# Led_Strip_5630.net
KiCad netlist of a schematic drawn in Altium Designer
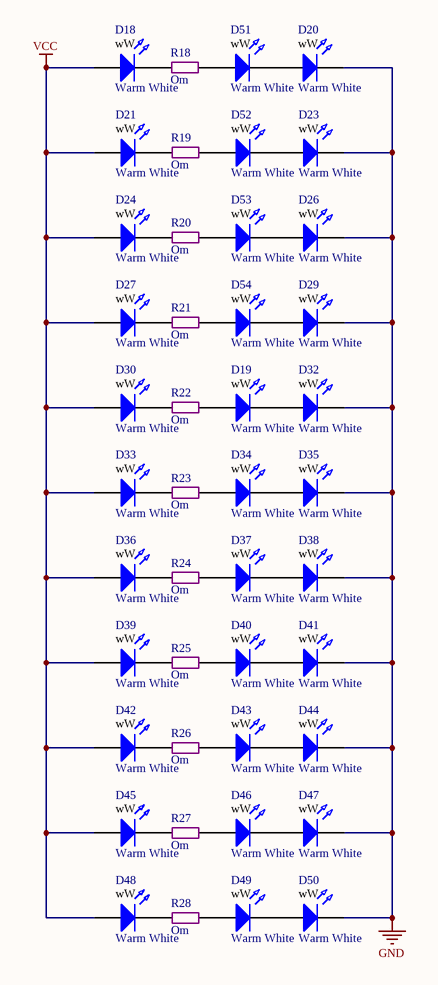
[diagram p0: Led Strip 5630.SchDoc]

(export (version "E")
  (design (tool "Eeschema 10.0.6"))
  (components
    (comp (ref "D18")
      (value "Warm White")
      (footprint "LED:LED SMD 5730 White")
      (description "?3v ?20mA")
      (libsource (lib "LED") (part "Led SMD White Warm"))
    )
    (comp (ref "D19")
      (value "Warm White")
      (footprint "LED:LED SMD 5730 White")
      (description "?3v ?20mA")
      (libsource (lib "LED") (part "Led SMD White Warm"))
    )
    (comp (ref "D20")
      (value "Warm White")
      (footprint "LED:LED SMD 5730 White")
      (description "?3v ?20mA")
      (libsource (lib "LED") (part "Led SMD White Warm"))
    )
    (comp (ref "D21")
      (value "Warm White")
      (footprint "LED:LED SMD 5730 White")
      (description "?3v ?20mA")
      (libsource (lib "LED") (part "Led SMD White Warm"))
    )
    (comp (ref "D23")
      (value "Warm White")
      (footprint "LED:LED SMD 5730 White")
      (description "?3v ?20mA")
      (libsource (lib "LED") (part "Led SMD White Warm"))
    )
    (comp (ref "D24")
      (value "Warm White")
      (footprint "LED:LED SMD 5730 White")
      (description "?3v ?20mA")
      (libsource (lib "LED") (part "Led SMD White Warm"))
    )
    (comp (ref "D26")
      (value "Warm White")
      (footprint "LED:LED SMD 5730 White")
      (description "?3v ?20mA")
      (libsource (lib "LED") (part "Led SMD White Warm"))
    )
    (comp (ref "D27")
      (value "Warm White")
      (footprint "LED:LED SMD 5730 White")
      (description "?3v ?20mA")
      (libsource (lib "LED") (part "Led SMD White Warm"))
    )
    (comp (ref "D29")
      (value "Warm White")
      (footprint "LED:LED SMD 5730 White")
      (description "?3v ?20mA")
      (libsource (lib "LED") (part "Led SMD White Warm"))
    )
    (comp (ref "D30")
      (value "Warm White")
      (footprint "LED:LED SMD 5730 White")
      (description "?3v ?20mA")
      (libsource (lib "LED") (part "Led SMD White Warm"))
    )
    (comp (ref "D32")
      (value "Warm White")
      (footprint "LED:LED SMD 5730 White")
      (description "?3v ?20mA")
      (libsource (lib "LED") (part "Led SMD White Warm"))
    )
    (comp (ref "D33")
      (value "Warm White")
      (footprint "LED:LED SMD 5730 White")
      (description "?3v ?20mA")
      (libsource (lib "LED") (part "Led SMD White Warm"))
    )
    (comp (ref "D34")
      (value "Warm White")
      (footprint "LED:LED SMD 5730 White")
      (description "?3v ?20mA")
      (libsource (lib "LED") (part "Led SMD White Warm"))
    )
    (comp (ref "D35")
      (value "Warm White")
      (footprint "LED:LED SMD 5730 White")
      (description "?3v ?20mA")
      (libsource (lib "LED") (part "Led SMD White Warm"))
    )
    (comp (ref "D36")
      (value "Warm White")
      (footprint "LED:LED SMD 5730 White")
      (description "?3v ?20mA")
      (libsource (lib "LED") (part "Led SMD White Warm"))
    )
    (comp (ref "D37")
      (value "Warm White")
      (footprint "LED:LED SMD 5730 White")
      (description "?3v ?20mA")
      (libsource (lib "LED") (part "Led SMD White Warm"))
    )
    (comp (ref "D38")
      (value "Warm White")
      (footprint "LED:LED SMD 5730 White")
      (description "?3v ?20mA")
      (libsource (lib "LED") (part "Led SMD White Warm"))
    )
    (comp (ref "D39")
      (value "Warm White")
      (footprint "LED:LED SMD 5730 White")
      (description "?3v ?20mA")
      (libsource (lib "LED") (part "Led SMD White Warm"))
    )
    (comp (ref "D40")
      (value "Warm White")
      (footprint "LED:LED SMD 5730 White")
      (description "?3v ?20mA")
      (libsource (lib "LED") (part "Led SMD White Warm"))
    )
    (comp (ref "D41")
      (value "Warm White")
      (footprint "LED:LED SMD 5730 White")
      (description "?3v ?20mA")
      (libsource (lib "LED") (part "Led SMD White Warm"))
    )
    (comp (ref "D42")
      (value "Warm White")
      (footprint "LED:LED SMD 5730 White")
      (description "?3v ?20mA")
      (libsource (lib "LED") (part "Led SMD White Warm"))
    )
    (comp (ref "D43")
      (value "Warm White")
      (footprint "LED:LED SMD 5730 White")
      (description "?3v ?20mA")
      (libsource (lib "LED") (part "Led SMD White Warm"))
    )
    (comp (ref "D44")
      (value "Warm White")
      (footprint "LED:LED SMD 5730 White")
      (description "?3v ?20mA")
      (libsource (lib "LED") (part "Led SMD White Warm"))
    )
    (comp (ref "D45")
      (value "Warm White")
      (footprint "LED:LED SMD 5730 White")
      (description "?3v ?20mA")
      (libsource (lib "LED") (part "Led SMD White Warm"))
    )
    (comp (ref "D46")
      (value "Warm White")
      (footprint "LED:LED SMD 5730 White")
      (description "?3v ?20mA")
      (libsource (lib "LED") (part "Led SMD White Warm"))
    )
    (comp (ref "D47")
      (value "Warm White")
      (footprint "LED:LED SMD 5730 White")
      (description "?3v ?20mA")
      (libsource (lib "LED") (part "Led SMD White Warm"))
    )
    (comp (ref "D48")
      (value "Warm White")
      (footprint "LED:LED SMD 5730 White")
      (description "?3v ?20mA")
      (libsource (lib "LED") (part "Led SMD White Warm"))
    )
    (comp (ref "D49")
      (value "Warm White")
      (footprint "LED:LED SMD 5730 White")
      (description "?3v ?20mA")
      (libsource (lib "LED") (part "Led SMD White Warm"))
    )
    (comp (ref "D50")
      (value "Warm White")
      (footprint "LED:LED SMD 5730 White")
      (description "?3v ?20mA")
      (libsource (lib "LED") (part "Led SMD White Warm"))
    )
    (comp (ref "D51")
      (value "Warm White")
      (footprint "LED:LED SMD 5730 White")
      (description "?3v ?20mA")
      (libsource (lib "LED") (part "Led SMD White Warm"))
    )
    (comp (ref "D52")
      (value "Warm White")
      (footprint "LED:LED SMD 5730 White")
      (description "?3v ?20mA")
      (libsource (lib "LED") (part "Led SMD White Warm"))
    )
    (comp (ref "D53")
      (value "Warm White")
      (footprint "LED:LED SMD 5730 White")
      (description "?3v ?20mA")
      (libsource (lib "LED") (part "Led SMD White Warm"))
    )
    (comp (ref "D54")
      (value "Warm White")
      (footprint "LED:LED SMD 5730 White")
      (description "?3v ?20mA")
      (libsource (lib "LED") (part "Led SMD White Warm"))
    )
    (comp (ref "R18")
      (value "Om")
      (footprint "PassiveComponents:SMD 1206 (3216)")
      (libsource (lib "PassiveComponents") (part "Res SMD 1206"))
    )
    (comp (ref "R19")
      (value "Om")
      (footprint "PassiveComponents:SMD 1206 (3216)")
      (libsource (lib "PassiveComponents") (part "Res SMD 1206"))
    )
    (comp (ref "R20")
      (value "Om")
      (footprint "PassiveComponents:SMD 1206 (3216)")
      (libsource (lib "PassiveComponents") (part "Res SMD 1206"))
    )
    (comp (ref "R21")
      (value "Om")
      (footprint "PassiveComponents:SMD 1206 (3216)")
      (libsource (lib "PassiveComponents") (part "Res SMD 1206"))
    )
    (comp (ref "R22")
      (value "Om")
      (footprint "PassiveComponents:SMD 1206 (3216)")
      (libsource (lib "PassiveComponents") (part "Res SMD 1206"))
    )
    (comp (ref "R23")
      (value "Om")
      (footprint "PassiveComponents:SMD 1206 (3216)")
      (libsource (lib "PassiveComponents") (part "Res SMD 1206"))
    )
    (comp (ref "R24")
      (value "Om")
      (footprint "PassiveComponents:SMD 1206 (3216)")
      (libsource (lib "PassiveComponents") (part "Res SMD 1206"))
    )
    (comp (ref "R25")
      (value "Om")
      (footprint "PassiveComponents:SMD 1206 (3216)")
      (libsource (lib "PassiveComponents") (part "Res SMD 1206"))
    )
    (comp (ref "R26")
      (value "Om")
      (footprint "PassiveComponents:SMD 1206 (3216)")
      (libsource (lib "PassiveComponents") (part "Res SMD 1206"))
    )
    (comp (ref "R27")
      (value "Om")
      (footprint "PassiveComponents:SMD 1206 (3216)")
      (libsource (lib "PassiveComponents") (part "Res SMD 1206"))
    )
    (comp (ref "R28")
      (value "Om")
      (footprint "PassiveComponents:SMD 1206 (3216)")
      (libsource (lib "PassiveComponents") (part "Res SMD 1206"))
    )
  )
  (nets
    (net (code "1") (name "GND") (class "Default")
      (node (ref "D20") (pin "K") (pinfunction "K_K") (pintype "passive"))
      (node (ref "D23") (pin "K") (pinfunction "K_K") (pintype "passive"))
      (node (ref "D26") (pin "K") (pinfunction "K_K") (pintype "passive"))
      (node (ref "D29") (pin "K") (pinfunction "K_K") (pintype "passive"))
      (node (ref "D32") (pin "K") (pinfunction "K_K") (pintype "passive"))
      (node (ref "D35") (pin "K") (pinfunction "K_K") (pintype "passive"))
      (node (ref "D38") (pin "K") (pinfunction "K_K") (pintype "passive"))
      (node (ref "D41") (pin "K") (pinfunction "K_K") (pintype "passive"))
      (node (ref "D44") (pin "K") (pinfunction "K_K") (pintype "passive"))
      (node (ref "D47") (pin "K") (pinfunction "K_K") (pintype "passive"))
      (node (ref "D50") (pin "K") (pinfunction "K_K") (pintype "passive"))
    )
    (net (code "2") (name "Net-(D18-PadK)") (class "Default")
      (node (ref "D18") (pin "K") (pinfunction "K_K") (pintype "passive"))
      (node (ref "R18") (pin "1") (pinfunction "1_1") (pintype "passive"))
    )
    (net (code "3") (name "Net-(D19-PadA)") (class "Default")
      (node (ref "D19") (pin "A") (pinfunction "A_A") (pintype "passive"))
      (node (ref "R22") (pin "2") (pinfunction "2_2") (pintype "passive"))
    )
    (net (code "4") (name "Net-(D19-PadK)") (class "Default")
      (node (ref "D19") (pin "K") (pinfunction "K_K") (pintype "passive"))
      (node (ref "D32") (pin "A") (pinfunction "A_A") (pintype "passive"))
    )
    (net (code "5") (name "Net-(D20-PadA)") (class "Default")
      (node (ref "D20") (pin "A") (pinfunction "A_A") (pintype "passive"))
      (node (ref "D51") (pin "K") (pinfunction "K_K") (pintype "passive"))
    )
    (net (code "6") (name "Net-(D21-PadK)") (class "Default")
      (node (ref "D21") (pin "K") (pinfunction "K_K") (pintype "passive"))
      (node (ref "R19") (pin "1") (pinfunction "1_1") (pintype "passive"))
    )
    (net (code "7") (name "Net-(D23-PadA)") (class "Default")
      (node (ref "D23") (pin "A") (pinfunction "A_A") (pintype "passive"))
      (node (ref "D52") (pin "K") (pinfunction "K_K") (pintype "passive"))
    )
    (net (code "8") (name "Net-(D24-PadK)") (class "Default")
      (node (ref "D24") (pin "K") (pinfunction "K_K") (pintype "passive"))
      (node (ref "R20") (pin "1") (pinfunction "1_1") (pintype "passive"))
    )
    (net (code "9") (name "Net-(D26-PadA)") (class "Default")
      (node (ref "D26") (pin "A") (pinfunction "A_A") (pintype "passive"))
      (node (ref "D53") (pin "K") (pinfunction "K_K") (pintype "passive"))
    )
    (net (code "10") (name "Net-(D27-PadK)") (class "Default")
      (node (ref "D27") (pin "K") (pinfunction "K_K") (pintype "passive"))
      (node (ref "R21") (pin "1") (pinfunction "1_1") (pintype "passive"))
    )
    (net (code "11") (name "Net-(D29-PadA)") (class "Default")
      (node (ref "D29") (pin "A") (pinfunction "A_A") (pintype "passive"))
      (node (ref "D54") (pin "K") (pinfunction "K_K") (pintype "passive"))
    )
    (net (code "12") (name "Net-(D30-PadK)") (class "Default")
      (node (ref "D30") (pin "K") (pinfunction "K_K") (pintype "passive"))
      (node (ref "R22") (pin "1") (pinfunction "1_1") (pintype "passive"))
    )
    (net (code "13") (name "Net-(D33-PadK)") (class "Default")
      (node (ref "D33") (pin "K") (pinfunction "K_K") (pintype "passive"))
      (node (ref "R23") (pin "1") (pinfunction "1_1") (pintype "passive"))
    )
    (net (code "14") (name "Net-(D34-PadA)") (class "Default")
      (node (ref "D34") (pin "A") (pinfunction "A_A") (pintype "passive"))
      (node (ref "R23") (pin "2") (pinfunction "2_2") (pintype "passive"))
    )
    (net (code "15") (name "Net-(D34-PadK)") (class "Default")
      (node (ref "D34") (pin "K") (pinfunction "K_K") (pintype "passive"))
      (node (ref "D35") (pin "A") (pinfunction "A_A") (pintype "passive"))
    )
    (net (code "16") (name "Net-(D36-PadK)") (class "Default")
      (node (ref "D36") (pin "K") (pinfunction "K_K") (pintype "passive"))
      (node (ref "R24") (pin "1") (pinfunction "1_1") (pintype "passive"))
    )
    (net (code "17") (name "Net-(D37-PadA)") (class "Default")
      (node (ref "D37") (pin "A") (pinfunction "A_A") (pintype "passive"))
      (node (ref "R24") (pin "2") (pinfunction "2_2") (pintype "passive"))
    )
    (net (code "18") (name "Net-(D37-PadK)") (class "Default")
      (node (ref "D37") (pin "K") (pinfunction "K_K") (pintype "passive"))
      (node (ref "D38") (pin "A") (pinfunction "A_A") (pintype "passive"))
    )
    (net (code "19") (name "Net-(D39-PadK)") (class "Default")
      (node (ref "D39") (pin "K") (pinfunction "K_K") (pintype "passive"))
      (node (ref "R25") (pin "1") (pinfunction "1_1") (pintype "passive"))
    )
    (net (code "20") (name "Net-(D40-PadA)") (class "Default")
      (node (ref "D40") (pin "A") (pinfunction "A_A") (pintype "passive"))
      (node (ref "R25") (pin "2") (pinfunction "2_2") (pintype "passive"))
    )
    (net (code "21") (name "Net-(D40-PadK)") (class "Default")
      (node (ref "D40") (pin "K") (pinfunction "K_K") (pintype "passive"))
      (node (ref "D41") (pin "A") (pinfunction "A_A") (pintype "passive"))
    )
    (net (code "22") (name "Net-(D42-PadK)") (class "Default")
      (node (ref "D42") (pin "K") (pinfunction "K_K") (pintype "passive"))
      (node (ref "R26") (pin "1") (pinfunction "1_1") (pintype "passive"))
    )
    (net (code "23") (name "Net-(D43-PadA)") (class "Default")
      (node (ref "D43") (pin "A") (pinfunction "A_A") (pintype "passive"))
      (node (ref "R26") (pin "2") (pinfunction "2_2") (pintype "passive"))
    )
    (net (code "24") (name "Net-(D43-PadK)") (class "Default")
      (node (ref "D43") (pin "K") (pinfunction "K_K") (pintype "passive"))
      (node (ref "D44") (pin "A") (pinfunction "A_A") (pintype "passive"))
    )
    (net (code "25") (name "Net-(D45-PadK)") (class "Default")
      (node (ref "D45") (pin "K") (pinfunction "K_K") (pintype "passive"))
      (node (ref "R27") (pin "1") (pinfunction "1_1") (pintype "passive"))
    )
    (net (code "26") (name "Net-(D46-PadA)") (class "Default")
      (node (ref "D46") (pin "A") (pinfunction "A_A") (pintype "passive"))
      (node (ref "R27") (pin "2") (pinfunction "2_2") (pintype "passive"))
    )
    (net (code "27") (name "Net-(D46-PadK)") (class "Default")
      (node (ref "D46") (pin "K") (pinfunction "K_K") (pintype "passive"))
      (node (ref "D47") (pin "A") (pinfunction "A_A") (pintype "passive"))
    )
    (net (code "28") (name "Net-(D48-PadK)") (class "Default")
      (node (ref "D48") (pin "K") (pinfunction "K_K") (pintype "passive"))
      (node (ref "R28") (pin "1") (pinfunction "1_1") (pintype "passive"))
    )
    (net (code "29") (name "Net-(D49-PadA)") (class "Default")
      (node (ref "D49") (pin "A") (pinfunction "A_A") (pintype "passive"))
      (node (ref "R28") (pin "2") (pinfunction "2_2") (pintype "passive"))
    )
    (net (code "30") (name "Net-(D49-PadK)") (class "Default")
      (node (ref "D49") (pin "K") (pinfunction "K_K") (pintype "passive"))
      (node (ref "D50") (pin "A") (pinfunction "A_A") (pintype "passive"))
    )
    (net (code "31") (name "Net-(D51-PadA)") (class "Default")
      (node (ref "D51") (pin "A") (pinfunction "A_A") (pintype "passive"))
      (node (ref "R18") (pin "2") (pinfunction "2_2") (pintype "passive"))
    )
    (net (code "32") (name "Net-(D52-PadA)") (class "Default")
      (node (ref "D52") (pin "A") (pinfunction "A_A") (pintype "passive"))
      (node (ref "R19") (pin "2") (pinfunction "2_2") (pintype "passive"))
    )
    (net (code "33") (name "Net-(D53-PadA)") (class "Default")
      (node (ref "D53") (pin "A") (pinfunction "A_A") (pintype "passive"))
      (node (ref "R20") (pin "2") (pinfunction "2_2") (pintype "passive"))
    )
    (net (code "34") (name "Net-(D54-PadA)") (class "Default")
      (node (ref "D54") (pin "A") (pinfunction "A_A") (pintype "passive"))
      (node (ref "R21") (pin "2") (pinfunction "2_2") (pintype "passive"))
    )
    (net (code "35") (name "VCC") (class "Default")
      (node (ref "D18") (pin "A") (pinfunction "A_A") (pintype "passive"))
      (node (ref "D21") (pin "A") (pinfunction "A_A") (pintype "passive"))
      (node (ref "D24") (pin "A") (pinfunction "A_A") (pintype "passive"))
      (node (ref "D27") (pin "A") (pinfunction "A_A") (pintype "passive"))
      (node (ref "D30") (pin "A") (pinfunction "A_A") (pintype "passive"))
      (node (ref "D33") (pin "A") (pinfunction "A_A") (pintype "passive"))
      (node (ref "D36") (pin "A") (pinfunction "A_A") (pintype "passive"))
      (node (ref "D39") (pin "A") (pinfunction "A_A") (pintype "passive"))
      (node (ref "D42") (pin "A") (pinfunction "A_A") (pintype "passive"))
      (node (ref "D45") (pin "A") (pinfunction "A_A") (pintype "passive"))
      (node (ref "D48") (pin "A") (pinfunction "A_A") (pintype "passive"))
    )
  )
)
